# ReceiverR3.net
KiCad netlist of a schematic drawn in EAGLE
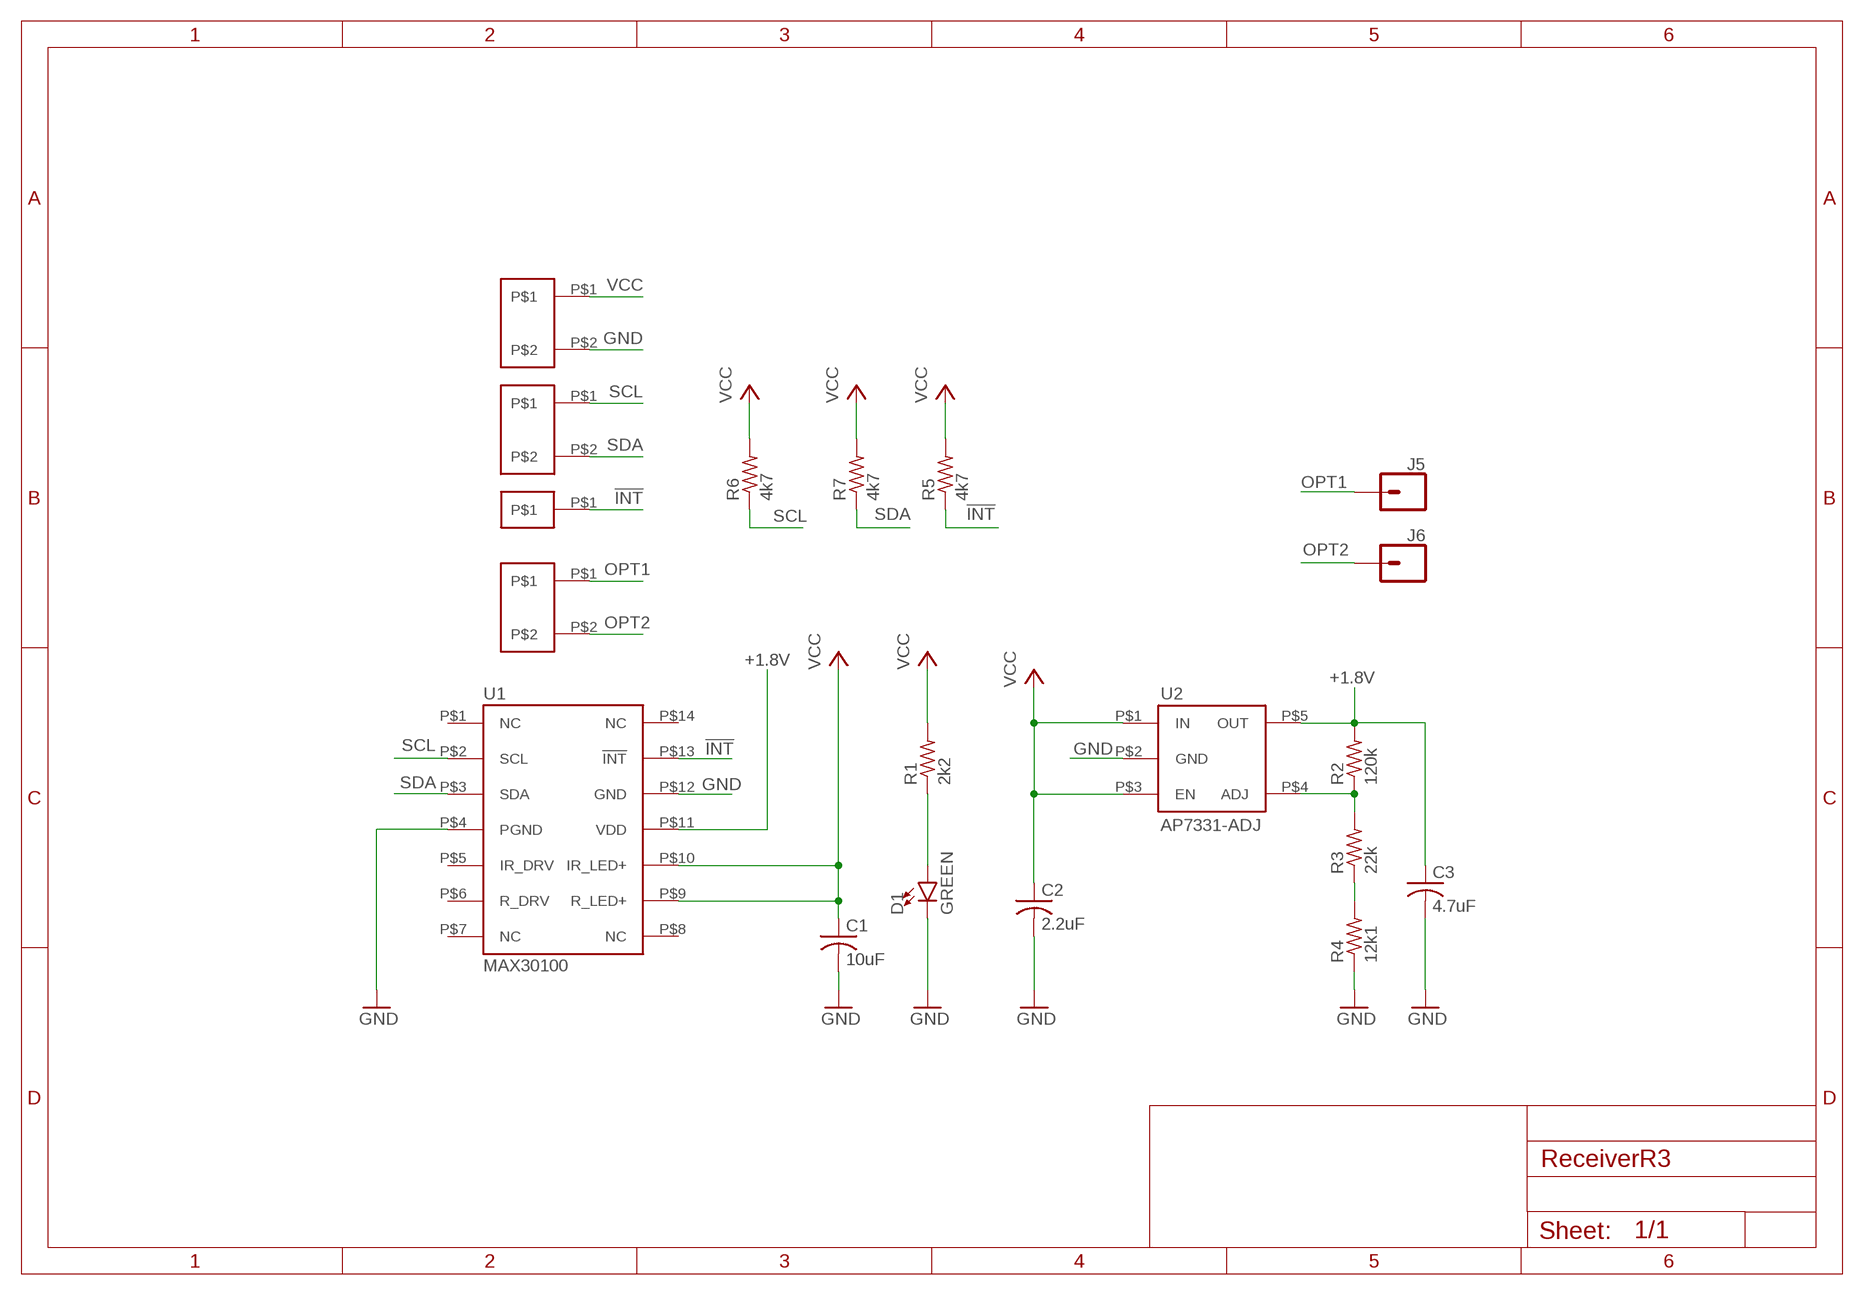
[diagram p0: schematic, sheet 1]

(export (version "E")
  (design (tool "Eeschema 10.0.6"))
  (components
    (comp (ref "C1")
      (value "10uF")
      (footprint "eagle-import:C0805")
      (libsource (lib "eagle-import") (part "C-USC0805"))
    )
    (comp (ref "C2")
      (value "2.2uF")
      (footprint "eagle-import:C0805")
      (libsource (lib "eagle-import") (part "C-USC0805"))
    )
    (comp (ref "C3")
      (value "4.7uF")
      (footprint "eagle-import:C0805")
      (libsource (lib "eagle-import") (part "C-USC0805"))
    )
    (comp (ref "D1")
      (value "GREEN")
      (footprint "eagle-import:LED-0603")
      (libsource (lib "eagle-import") (part "LED-GREEN0603"))
    )
    (comp (ref "J1")
      (value "SOLDERPAD1X2")
      (footprint "eagle-import:SOLDERPAD1X2")
      (libsource (lib "eagle-import") (part "SOLDERPAD1X2"))
    )
    (comp (ref "J2")
      (value "SOLDERPAD1X2")
      (footprint "eagle-import:SOLDERPAD1X2")
      (libsource (lib "eagle-import") (part "SOLDERPAD1X2"))
    )
    (comp (ref "J3")
      (value "SOLDERPAD1X2")
      (footprint "eagle-import:SOLDERPAD1X2")
      (libsource (lib "eagle-import") (part "SOLDERPAD1X2"))
    )
    (comp (ref "J4")
      (value "SOLDERPAD1X1")
      (footprint "eagle-import:SOLDERPAD1X1")
      (libsource (lib "eagle-import") (part "SOLDERPAD1X1"))
    )
    (comp (ref "J5")
      (value "CONN_01")
      (footprint "eagle-import:1X01")
      (libsource (lib "eagle-import") (part "CONN_01"))
    )
    (comp (ref "J6")
      (value "CONN_01")
      (footprint "eagle-import:1X01")
      (libsource (lib "eagle-import") (part "CONN_01"))
    )
    (comp (ref "R1")
      (value "2k2")
      (footprint "eagle-import:R0805")
      (libsource (lib "eagle-import") (part "R-US_R0805"))
    )
    (comp (ref "R2")
      (value "120k")
      (footprint "eagle-import:R0805")
      (libsource (lib "eagle-import") (part "R-US_R0805"))
    )
    (comp (ref "R3")
      (value "22k")
      (footprint "eagle-import:R0805")
      (libsource (lib "eagle-import") (part "R-US_R0805"))
    )
    (comp (ref "R4")
      (value "12k1")
      (footprint "eagle-import:R0805")
      (libsource (lib "eagle-import") (part "R-US_R0805"))
    )
    (comp (ref "R5")
      (value "4k7")
      (footprint "eagle-import:R0805")
      (libsource (lib "eagle-import") (part "R-US_R0805"))
    )
    (comp (ref "R6")
      (value "4k7")
      (footprint "eagle-import:R0805")
      (libsource (lib "eagle-import") (part "R-US_R0805"))
    )
    (comp (ref "R7")
      (value "4k7")
      (footprint "eagle-import:R0805")
      (libsource (lib "eagle-import") (part "R-US_R0805"))
    )
    (comp (ref "U1")
      (value "MAX30100")
      (footprint "eagle-import:14OESIP")
      (libsource (lib "eagle-import") (part "MAX30100"))
    )
    (comp (ref "U2")
      (value "AP7331-ADJ")
      (footprint "eagle-import:SOT25")
      (libsource (lib "eagle-import") (part "AP7331-ADJ"))
    )
  )
  (nets
    (net (code "1") (name "/+1.8V") (class "Default")
      (node (ref "C3") (pin "1") (pinfunction "1_1") (pintype "passive"))
      (node (ref "R2") (pin "2") (pinfunction "2_2") (pintype "passive"))
      (node (ref "U1") (pin "P$11") (pinfunction "VDD_P$11") (pintype "bidirectional"))
      (node (ref "U2") (pin "P$5") (pinfunction "OUT_P$5") (pintype "bidirectional"))
    )
    (net (code "2") (name "/OPT1") (class "Default")
      (node (ref "J1") (pin "P$1") (pinfunction "P$1_P$1") (pintype "bidirectional"))
      (node (ref "J5") (pin "1") (pinfunction "1_1") (pintype "passive"))
    )
    (net (code "3") (name "/OPT2") (class "Default")
      (node (ref "J1") (pin "P$2") (pinfunction "P$2_P$2") (pintype "bidirectional"))
      (node (ref "J6") (pin "1") (pinfunction "1_1") (pintype "passive"))
    )
    (net (code "4") (name "/SCL") (class "Default")
      (node (ref "J3") (pin "P$1") (pinfunction "P$1_P$1") (pintype "bidirectional"))
      (node (ref "R6") (pin "1") (pinfunction "1_1") (pintype "passive"))
      (node (ref "U1") (pin "P$2") (pinfunction "SCL_P$2") (pintype "bidirectional"))
    )
    (net (code "5") (name "/SDA") (class "Default")
      (node (ref "J3") (pin "P$2") (pinfunction "P$2_P$2") (pintype "bidirectional"))
      (node (ref "R7") (pin "1") (pinfunction "1_1") (pintype "passive"))
      (node (ref "U1") (pin "P$3") (pinfunction "SDA_P$3") (pintype "bidirectional"))
    )
    (net (code "6") (name "/~{INT}") (class "Default")
      (node (ref "J4") (pin "P$1") (pinfunction "P$1_P$1") (pintype "bidirectional"))
      (node (ref "R5") (pin "1") (pinfunction "1_1") (pintype "passive"))
      (node (ref "U1") (pin "P$13") (pinfunction "~{INT}_P$13") (pintype "bidirectional"))
    )
    (net (code "7") (name "GND") (class "Default")
      (node (ref "C1") (pin "2") (pinfunction "2_2") (pintype "passive"))
      (node (ref "C2") (pin "2") (pinfunction "2_2") (pintype "passive"))
      (node (ref "C3") (pin "2") (pinfunction "2_2") (pintype "passive"))
      (node (ref "D1") (pin "C") (pinfunction "C_C") (pintype "passive"))
      (node (ref "J2") (pin "P$2") (pinfunction "P$2_P$2") (pintype "bidirectional"))
      (node (ref "R4") (pin "1") (pinfunction "1_1") (pintype "passive"))
      (node (ref "U1") (pin "P$12") (pinfunction "GND_P$12") (pintype "bidirectional"))
      (node (ref "U1") (pin "P$4") (pinfunction "PGND_P$4") (pintype "bidirectional"))
      (node (ref "U2") (pin "P$2") (pinfunction "GND_P$2") (pintype "bidirectional"))
    )
    (net (code "8") (name "Net-(D1-PadA)") (class "Default")
      (node (ref "D1") (pin "A") (pinfunction "A_A") (pintype "passive"))
      (node (ref "R1") (pin "1") (pinfunction "1_1") (pintype "passive"))
    )
    (net (code "9") (name "Net-(R3-Pad1)") (class "Default")
      (node (ref "R3") (pin "1") (pinfunction "1_1") (pintype "passive"))
      (node (ref "R4") (pin "2") (pinfunction "2_2") (pintype "passive"))
    )
    (net (code "10") (name "Net-(U2-ADJ)") (class "Default")
      (node (ref "R2") (pin "1") (pinfunction "1_1") (pintype "passive"))
      (node (ref "R3") (pin "2") (pinfunction "2_2") (pintype "passive"))
      (node (ref "U2") (pin "P$4") (pinfunction "ADJ_P$4") (pintype "bidirectional"))
    )
    (net (code "11") (name "VCC") (class "Default")
      (node (ref "C1") (pin "1") (pinfunction "1_1") (pintype "passive"))
      (node (ref "C2") (pin "1") (pinfunction "1_1") (pintype "passive"))
      (node (ref "J2") (pin "P$1") (pinfunction "P$1_P$1") (pintype "bidirectional"))
      (node (ref "R1") (pin "2") (pinfunction "2_2") (pintype "passive"))
      (node (ref "R5") (pin "2") (pinfunction "2_2") (pintype "passive"))
      (node (ref "R6") (pin "2") (pinfunction "2_2") (pintype "passive"))
      (node (ref "R7") (pin "2") (pinfunction "2_2") (pintype "passive"))
      (node (ref "U1") (pin "P$10") (pinfunction "IR_LED+_P$10") (pintype "bidirectional"))
      (node (ref "U1") (pin "P$9") (pinfunction "R_LED+_P$9") (pintype "bidirectional"))
      (node (ref "U2") (pin "P$1") (pinfunction "IN_P$1") (pintype "bidirectional"))
      (node (ref "U2") (pin "P$3") (pinfunction "EN_P$3") (pintype "bidirectional"))
    )
    (net (code "12") (name "unconnected-(U1-IR_DRV-PadP$5)") (class "Default")
      (node (ref "U1") (pin "P$5") (pinfunction "IR_DRV_P$5") (pintype "bidirectional"))
    )
    (net (code "13") (name "unconnected-(U1-NC-PadP$1)") (class "Default")
      (node (ref "U1") (pin "P$1") (pinfunction "NC_P$1") (pintype "bidirectional"))
    )
    (net (code "14") (name "unconnected-(U1-NC-PadP$7)") (class "Default")
      (node (ref "U1") (pin "P$7") (pinfunction "NC_P$7") (pintype "bidirectional"))
    )
    (net (code "15") (name "unconnected-(U1-NC-PadP$8)") (class "Default")
      (node (ref "U1") (pin "P$8") (pinfunction "NC_P$8") (pintype "bidirectional"))
    )
    (net (code "16") (name "unconnected-(U1-NC-PadP$14)") (class "Default")
      (node (ref "U1") (pin "P$14") (pinfunction "NC_P$14") (pintype "bidirectional"))
    )
    (net (code "17") (name "unconnected-(U1-R_DRV-PadP$6)") (class "Default")
      (node (ref "U1") (pin "P$6") (pinfunction "R_DRV_P$6") (pintype "bidirectional"))
    )
  )
)
